# schematicEagle.net
KiCad netlist of a schematic drawn in EAGLE
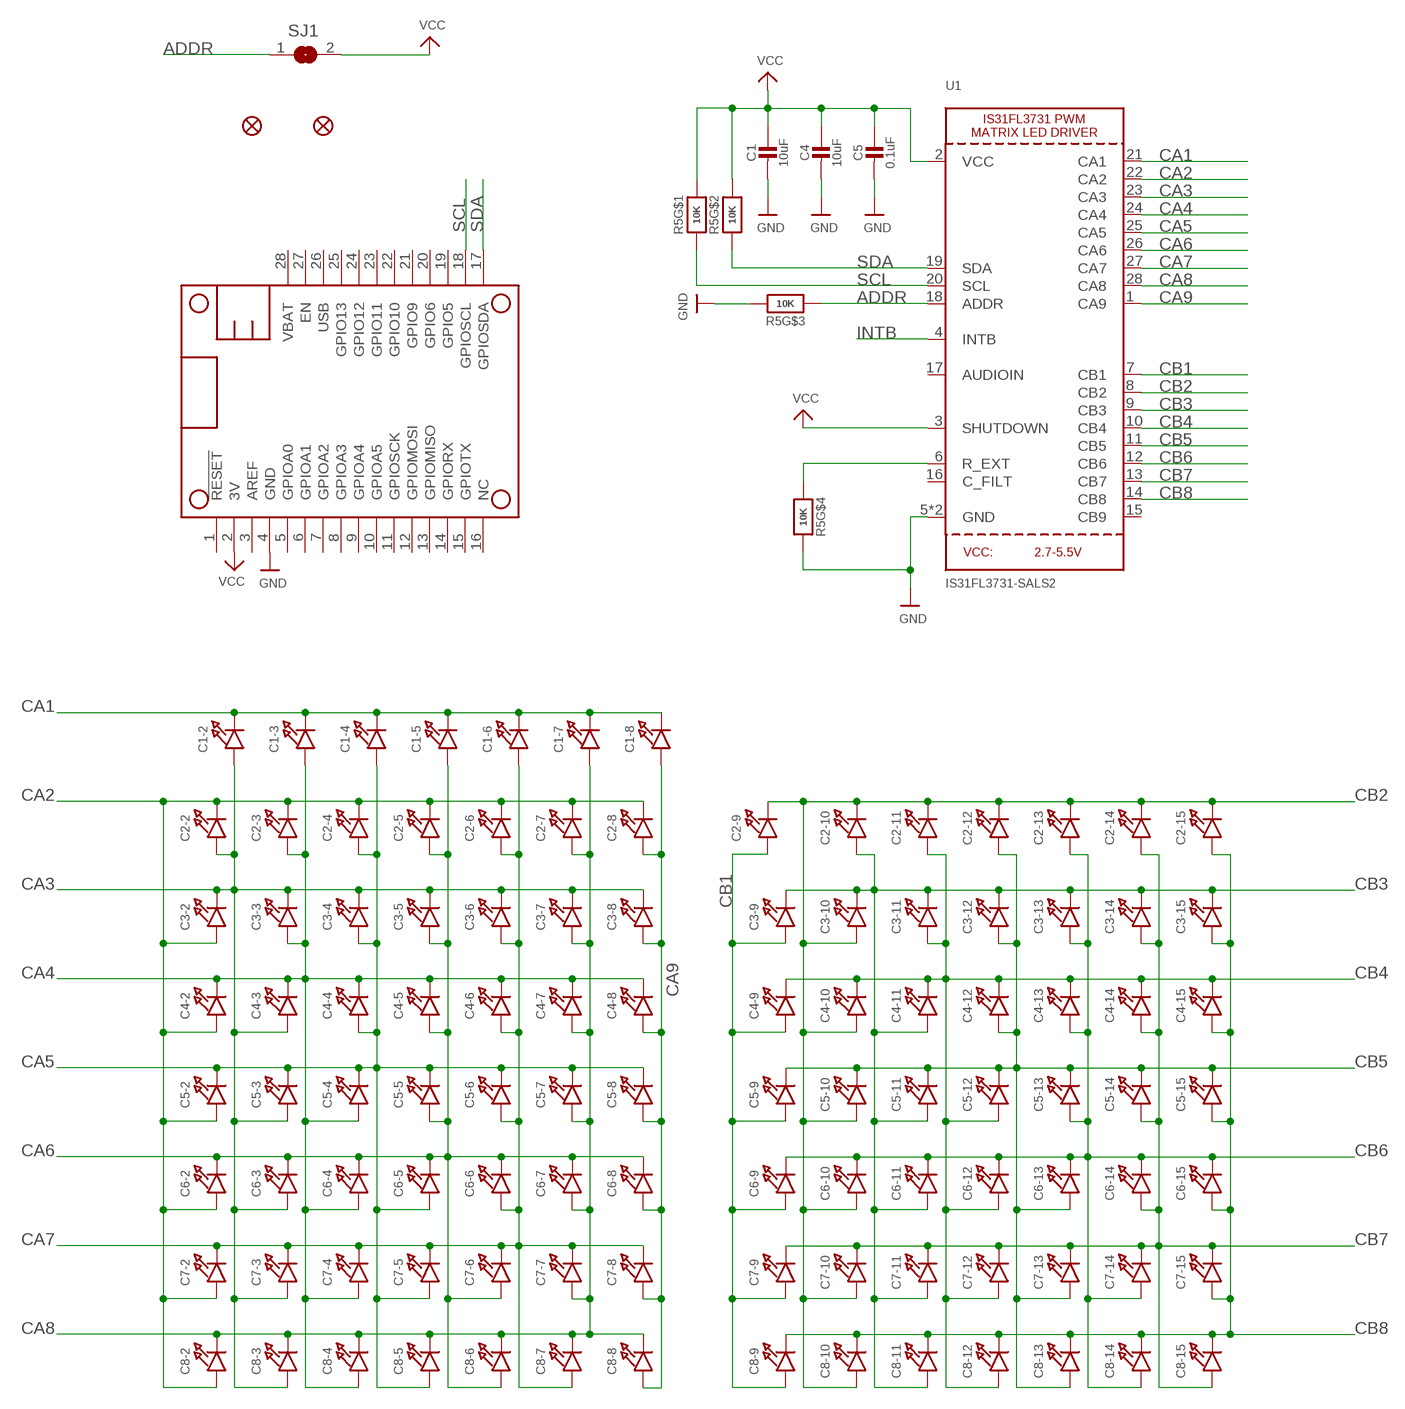
[diagram p0: schematic, sheet 1]

(export (version "E")
  (design (tool "Eeschema 10.0.6"))
  (components
    (comp (ref "C1")
      (value "10uF")
      (footprint "eagle-import:0805-NO")
      (libsource (lib "eagle-import") (part "CAP_CERAMIC0805-NOOUTLINE"))
    )
    (comp (ref "C1-2")
      (value "LED0603_NOOUTLINE")
      (footprint "eagle-import:CHIPLED_0603_NOOUTLINE")
      (libsource (lib "eagle-import") (part "LED0603_NOOUTLINE"))
    )
    (comp (ref "C1-3")
      (value "LED0603_NOOUTLINE")
      (footprint "eagle-import:CHIPLED_0603_NOOUTLINE")
      (libsource (lib "eagle-import") (part "LED0603_NOOUTLINE"))
    )
    (comp (ref "C1-4")
      (value "LED0603_NOOUTLINE")
      (footprint "eagle-import:CHIPLED_0603_NOOUTLINE")
      (libsource (lib "eagle-import") (part "LED0603_NOOUTLINE"))
    )
    (comp (ref "C1-5")
      (value "LED0603_NOOUTLINE")
      (footprint "eagle-import:CHIPLED_0603_NOOUTLINE")
      (libsource (lib "eagle-import") (part "LED0603_NOOUTLINE"))
    )
    (comp (ref "C1-6")
      (value "LED0603_NOOUTLINE")
      (footprint "eagle-import:CHIPLED_0603_NOOUTLINE")
      (libsource (lib "eagle-import") (part "LED0603_NOOUTLINE"))
    )
    (comp (ref "C1-7")
      (value "LED0603_NOOUTLINE")
      (footprint "eagle-import:CHIPLED_0603_NOOUTLINE")
      (libsource (lib "eagle-import") (part "LED0603_NOOUTLINE"))
    )
    (comp (ref "C1-8")
      (value "LED0603_NOOUTLINE")
      (footprint "eagle-import:CHIPLED_0603_NOOUTLINE")
      (libsource (lib "eagle-import") (part "LED0603_NOOUTLINE"))
    )
    (comp (ref "C2-2")
      (value "LED0603_NOOUTLINE")
      (footprint "eagle-import:CHIPLED_0603_NOOUTLINE")
      (libsource (lib "eagle-import") (part "LED0603_NOOUTLINE"))
    )
    (comp (ref "C2-3")
      (value "LED0603_NOOUTLINE")
      (footprint "eagle-import:CHIPLED_0603_NOOUTLINE")
      (libsource (lib "eagle-import") (part "LED0603_NOOUTLINE"))
    )
    (comp (ref "C2-4")
      (value "LED0603_NOOUTLINE")
      (footprint "eagle-import:CHIPLED_0603_NOOUTLINE")
      (libsource (lib "eagle-import") (part "LED0603_NOOUTLINE"))
    )
    (comp (ref "C2-5")
      (value "LED0603_NOOUTLINE")
      (footprint "eagle-import:CHIPLED_0603_NOOUTLINE")
      (libsource (lib "eagle-import") (part "LED0603_NOOUTLINE"))
    )
    (comp (ref "C2-6")
      (value "LED0603_NOOUTLINE")
      (footprint "eagle-import:CHIPLED_0603_NOOUTLINE")
      (libsource (lib "eagle-import") (part "LED0603_NOOUTLINE"))
    )
    (comp (ref "C2-7")
      (value "LED0603_NOOUTLINE")
      (footprint "eagle-import:CHIPLED_0603_NOOUTLINE")
      (libsource (lib "eagle-import") (part "LED0603_NOOUTLINE"))
    )
    (comp (ref "C2-8")
      (value "LED0603_NOOUTLINE")
      (footprint "eagle-import:CHIPLED_0603_NOOUTLINE")
      (libsource (lib "eagle-import") (part "LED0603_NOOUTLINE"))
    )
    (comp (ref "C2-9")
      (value "LED0603_NOOUTLINE")
      (footprint "eagle-import:CHIPLED_0603_NOOUTLINE")
      (libsource (lib "eagle-import") (part "LED0603_NOOUTLINE"))
    )
    (comp (ref "C2-10")
      (value "LED0603_NOOUTLINE")
      (footprint "eagle-import:CHIPLED_0603_NOOUTLINE")
      (libsource (lib "eagle-import") (part "LED0603_NOOUTLINE"))
    )
    (comp (ref "C2-11")
      (value "LED0603_NOOUTLINE")
      (footprint "eagle-import:CHIPLED_0603_NOOUTLINE")
      (libsource (lib "eagle-import") (part "LED0603_NOOUTLINE"))
    )
    (comp (ref "C2-12")
      (value "LED0603_NOOUTLINE")
      (footprint "eagle-import:CHIPLED_0603_NOOUTLINE")
      (libsource (lib "eagle-import") (part "LED0603_NOOUTLINE"))
    )
    (comp (ref "C2-13")
      (value "LED0603_NOOUTLINE")
      (footprint "eagle-import:CHIPLED_0603_NOOUTLINE")
      (libsource (lib "eagle-import") (part "LED0603_NOOUTLINE"))
    )
    (comp (ref "C2-14")
      (value "LED0603_NOOUTLINE")
      (footprint "eagle-import:CHIPLED_0603_NOOUTLINE")
      (libsource (lib "eagle-import") (part "LED0603_NOOUTLINE"))
    )
    (comp (ref "C2-15")
      (value "LED0603_NOOUTLINE")
      (footprint "eagle-import:CHIPLED_0603_NOOUTLINE")
      (libsource (lib "eagle-import") (part "LED0603_NOOUTLINE"))
    )
    (comp (ref "C3-2")
      (value "LED0603_NOOUTLINE")
      (footprint "eagle-import:CHIPLED_0603_NOOUTLINE")
      (libsource (lib "eagle-import") (part "LED0603_NOOUTLINE"))
    )
    (comp (ref "C3-3")
      (value "LED0603_NOOUTLINE")
      (footprint "eagle-import:CHIPLED_0603_NOOUTLINE")
      (libsource (lib "eagle-import") (part "LED0603_NOOUTLINE"))
    )
    (comp (ref "C3-4")
      (value "LED0603_NOOUTLINE")
      (footprint "eagle-import:CHIPLED_0603_NOOUTLINE")
      (libsource (lib "eagle-import") (part "LED0603_NOOUTLINE"))
    )
    (comp (ref "C3-5")
      (value "LED0603_NOOUTLINE")
      (footprint "eagle-import:CHIPLED_0603_NOOUTLINE")
      (libsource (lib "eagle-import") (part "LED0603_NOOUTLINE"))
    )
    (comp (ref "C3-6")
      (value "LED0603_NOOUTLINE")
      (footprint "eagle-import:CHIPLED_0603_NOOUTLINE")
      (libsource (lib "eagle-import") (part "LED0603_NOOUTLINE"))
    )
    (comp (ref "C3-7")
      (value "LED0603_NOOUTLINE")
      (footprint "eagle-import:CHIPLED_0603_NOOUTLINE")
      (libsource (lib "eagle-import") (part "LED0603_NOOUTLINE"))
    )
    (comp (ref "C3-8")
      (value "LED0603_NOOUTLINE")
      (footprint "eagle-import:CHIPLED_0603_NOOUTLINE")
      (libsource (lib "eagle-import") (part "LED0603_NOOUTLINE"))
    )
    (comp (ref "C3-9")
      (value "LED0603_NOOUTLINE")
      (footprint "eagle-import:CHIPLED_0603_NOOUTLINE")
      (libsource (lib "eagle-import") (part "LED0603_NOOUTLINE"))
    )
    (comp (ref "C3-10")
      (value "LED0603_NOOUTLINE")
      (footprint "eagle-import:CHIPLED_0603_NOOUTLINE")
      (libsource (lib "eagle-import") (part "LED0603_NOOUTLINE"))
    )
    (comp (ref "C3-11")
      (value "LED0603_NOOUTLINE")
      (footprint "eagle-import:CHIPLED_0603_NOOUTLINE")
      (libsource (lib "eagle-import") (part "LED0603_NOOUTLINE"))
    )
    (comp (ref "C3-12")
      (value "LED0603_NOOUTLINE")
      (footprint "eagle-import:CHIPLED_0603_NOOUTLINE")
      (libsource (lib "eagle-import") (part "LED0603_NOOUTLINE"))
    )
    (comp (ref "C3-13")
      (value "LED0603_NOOUTLINE")
      (footprint "eagle-import:CHIPLED_0603_NOOUTLINE")
      (libsource (lib "eagle-import") (part "LED0603_NOOUTLINE"))
    )
    (comp (ref "C3-14")
      (value "LED0603_NOOUTLINE")
      (footprint "eagle-import:CHIPLED_0603_NOOUTLINE")
      (libsource (lib "eagle-import") (part "LED0603_NOOUTLINE"))
    )
    (comp (ref "C3-15")
      (value "LED0603_NOOUTLINE")
      (footprint "eagle-import:CHIPLED_0603_NOOUTLINE")
      (libsource (lib "eagle-import") (part "LED0603_NOOUTLINE"))
    )
    (comp (ref "C4")
      (value "10uF")
      (footprint "eagle-import:0805-NO")
      (libsource (lib "eagle-import") (part "CAP_CERAMIC0805-NOOUTLINE"))
    )
    (comp (ref "C4-2")
      (value "LED0603_NOOUTLINE")
      (footprint "eagle-import:CHIPLED_0603_NOOUTLINE")
      (libsource (lib "eagle-import") (part "LED0603_NOOUTLINE"))
    )
    (comp (ref "C4-3")
      (value "LED0603_NOOUTLINE")
      (footprint "eagle-import:CHIPLED_0603_NOOUTLINE")
      (libsource (lib "eagle-import") (part "LED0603_NOOUTLINE"))
    )
    (comp (ref "C4-4")
      (value "LED0603_NOOUTLINE")
      (footprint "eagle-import:CHIPLED_0603_NOOUTLINE")
      (libsource (lib "eagle-import") (part "LED0603_NOOUTLINE"))
    )
    (comp (ref "C4-5")
      (value "LED0603_NOOUTLINE")
      (footprint "eagle-import:CHIPLED_0603_NOOUTLINE")
      (libsource (lib "eagle-import") (part "LED0603_NOOUTLINE"))
    )
    (comp (ref "C4-6")
      (value "LED0603_NOOUTLINE")
      (footprint "eagle-import:CHIPLED_0603_NOOUTLINE")
      (libsource (lib "eagle-import") (part "LED0603_NOOUTLINE"))
    )
    (comp (ref "C4-7")
      (value "LED0603_NOOUTLINE")
      (footprint "eagle-import:CHIPLED_0603_NOOUTLINE")
      (libsource (lib "eagle-import") (part "LED0603_NOOUTLINE"))
    )
    (comp (ref "C4-8")
      (value "LED0603_NOOUTLINE")
      (footprint "eagle-import:CHIPLED_0603_NOOUTLINE")
      (libsource (lib "eagle-import") (part "LED0603_NOOUTLINE"))
    )
    (comp (ref "C4-9")
      (value "LED0603_NOOUTLINE")
      (footprint "eagle-import:CHIPLED_0603_NOOUTLINE")
      (libsource (lib "eagle-import") (part "LED0603_NOOUTLINE"))
    )
    (comp (ref "C4-10")
      (value "LED0603_NOOUTLINE")
      (footprint "eagle-import:CHIPLED_0603_NOOUTLINE")
      (libsource (lib "eagle-import") (part "LED0603_NOOUTLINE"))
    )
    (comp (ref "C4-11")
      (value "LED0603_NOOUTLINE")
      (footprint "eagle-import:CHIPLED_0603_NOOUTLINE")
      (libsource (lib "eagle-import") (part "LED0603_NOOUTLINE"))
    )
    (comp (ref "C4-12")
      (value "LED0603_NOOUTLINE")
      (footprint "eagle-import:CHIPLED_0603_NOOUTLINE")
      (libsource (lib "eagle-import") (part "LED0603_NOOUTLINE"))
    )
    (comp (ref "C4-13")
      (value "LED0603_NOOUTLINE")
      (footprint "eagle-import:CHIPLED_0603_NOOUTLINE")
      (libsource (lib "eagle-import") (part "LED0603_NOOUTLINE"))
    )
    (comp (ref "C4-14")
      (value "LED0603_NOOUTLINE")
      (footprint "eagle-import:CHIPLED_0603_NOOUTLINE")
      (libsource (lib "eagle-import") (part "LED0603_NOOUTLINE"))
    )
    (comp (ref "C4-15")
      (value "LED0603_NOOUTLINE")
      (footprint "eagle-import:CHIPLED_0603_NOOUTLINE")
      (libsource (lib "eagle-import") (part "LED0603_NOOUTLINE"))
    )
    (comp (ref "C5")
      (value "0.1uF")
      (footprint "eagle-import:0805-NO")
      (libsource (lib "eagle-import") (part "CAP_CERAMIC0805-NOOUTLINE"))
    )
    (comp (ref "C5-2")
      (value "LED0603_NOOUTLINE")
      (footprint "eagle-import:CHIPLED_0603_NOOUTLINE")
      (libsource (lib "eagle-import") (part "LED0603_NOOUTLINE"))
    )
    (comp (ref "C5-3")
      (value "LED0603_NOOUTLINE")
      (footprint "eagle-import:CHIPLED_0603_NOOUTLINE")
      (libsource (lib "eagle-import") (part "LED0603_NOOUTLINE"))
    )
    (comp (ref "C5-4")
      (value "LED0603_NOOUTLINE")
      (footprint "eagle-import:CHIPLED_0603_NOOUTLINE")
      (libsource (lib "eagle-import") (part "LED0603_NOOUTLINE"))
    )
    (comp (ref "C5-5")
      (value "LED0603_NOOUTLINE")
      (footprint "eagle-import:CHIPLED_0603_NOOUTLINE")
      (libsource (lib "eagle-import") (part "LED0603_NOOUTLINE"))
    )
    (comp (ref "C5-6")
      (value "LED0603_NOOUTLINE")
      (footprint "eagle-import:CHIPLED_0603_NOOUTLINE")
      (libsource (lib "eagle-import") (part "LED0603_NOOUTLINE"))
    )
    (comp (ref "C5-7")
      (value "LED0603_NOOUTLINE")
      (footprint "eagle-import:CHIPLED_0603_NOOUTLINE")
      (libsource (lib "eagle-import") (part "LED0603_NOOUTLINE"))
    )
    (comp (ref "C5-8")
      (value "LED0603_NOOUTLINE")
      (footprint "eagle-import:CHIPLED_0603_NOOUTLINE")
      (libsource (lib "eagle-import") (part "LED0603_NOOUTLINE"))
    )
    (comp (ref "C5-9")
      (value "LED0603_NOOUTLINE")
      (footprint "eagle-import:CHIPLED_0603_NOOUTLINE")
      (libsource (lib "eagle-import") (part "LED0603_NOOUTLINE"))
    )
    (comp (ref "C5-10")
      (value "LED0603_NOOUTLINE")
      (footprint "eagle-import:CHIPLED_0603_NOOUTLINE")
      (libsource (lib "eagle-import") (part "LED0603_NOOUTLINE"))
    )
    (comp (ref "C5-11")
      (value "LED0603_NOOUTLINE")
      (footprint "eagle-import:CHIPLED_0603_NOOUTLINE")
      (libsource (lib "eagle-import") (part "LED0603_NOOUTLINE"))
    )
    (comp (ref "C5-12")
      (value "LED0603_NOOUTLINE")
      (footprint "eagle-import:CHIPLED_0603_NOOUTLINE")
      (libsource (lib "eagle-import") (part "LED0603_NOOUTLINE"))
    )
    (comp (ref "C5-13")
      (value "LED0603_NOOUTLINE")
      (footprint "eagle-import:CHIPLED_0603_NOOUTLINE")
      (libsource (lib "eagle-import") (part "LED0603_NOOUTLINE"))
    )
    (comp (ref "C5-14")
      (value "LED0603_NOOUTLINE")
      (footprint "eagle-import:CHIPLED_0603_NOOUTLINE")
      (libsource (lib "eagle-import") (part "LED0603_NOOUTLINE"))
    )
    (comp (ref "C5-15")
      (value "LED0603_NOOUTLINE")
      (footprint "eagle-import:CHIPLED_0603_NOOUTLINE")
      (libsource (lib "eagle-import") (part "LED0603_NOOUTLINE"))
    )
    (comp (ref "C6-2")
      (value "LED0603_NOOUTLINE")
      (footprint "eagle-import:CHIPLED_0603_NOOUTLINE")
      (libsource (lib "eagle-import") (part "LED0603_NOOUTLINE"))
    )
    (comp (ref "C6-3")
      (value "LED0603_NOOUTLINE")
      (footprint "eagle-import:CHIPLED_0603_NOOUTLINE")
      (libsource (lib "eagle-import") (part "LED0603_NOOUTLINE"))
    )
    (comp (ref "C6-4")
      (value "LED0603_NOOUTLINE")
      (footprint "eagle-import:CHIPLED_0603_NOOUTLINE")
      (libsource (lib "eagle-import") (part "LED0603_NOOUTLINE"))
    )
    (comp (ref "C6-5")
      (value "LED0603_NOOUTLINE")
      (footprint "eagle-import:CHIPLED_0603_NOOUTLINE")
      (libsource (lib "eagle-import") (part "LED0603_NOOUTLINE"))
    )
    (comp (ref "C6-6")
      (value "LED0603_NOOUTLINE")
      (footprint "eagle-import:CHIPLED_0603_NOOUTLINE")
      (libsource (lib "eagle-import") (part "LED0603_NOOUTLINE"))
    )
    (comp (ref "C6-7")
      (value "LED0603_NOOUTLINE")
      (footprint "eagle-import:CHIPLED_0603_NOOUTLINE")
      (libsource (lib "eagle-import") (part "LED0603_NOOUTLINE"))
    )
    (comp (ref "C6-8")
      (value "LED0603_NOOUTLINE")
      (footprint "eagle-import:CHIPLED_0603_NOOUTLINE")
      (libsource (lib "eagle-import") (part "LED0603_NOOUTLINE"))
    )
    (comp (ref "C6-9")
      (value "LED0603_NOOUTLINE")
      (footprint "eagle-import:CHIPLED_0603_NOOUTLINE")
      (libsource (lib "eagle-import") (part "LED0603_NOOUTLINE"))
    )
    (comp (ref "C6-10")
      (value "LED0603_NOOUTLINE")
      (footprint "eagle-import:CHIPLED_0603_NOOUTLINE")
      (libsource (lib "eagle-import") (part "LED0603_NOOUTLINE"))
    )
    (comp (ref "C6-11")
      (value "LED0603_NOOUTLINE")
      (footprint "eagle-import:CHIPLED_0603_NOOUTLINE")
      (libsource (lib "eagle-import") (part "LED0603_NOOUTLINE"))
    )
    (comp (ref "C6-12")
      (value "LED0603_NOOUTLINE")
      (footprint "eagle-import:CHIPLED_0603_NOOUTLINE")
      (libsource (lib "eagle-import") (part "LED0603_NOOUTLINE"))
    )
    (comp (ref "C6-13")
      (value "LED0603_NOOUTLINE")
      (footprint "eagle-import:CHIPLED_0603_NOOUTLINE")
      (libsource (lib "eagle-import") (part "LED0603_NOOUTLINE"))
    )
    (comp (ref "C6-14")
      (value "LED0603_NOOUTLINE")
      (footprint "eagle-import:CHIPLED_0603_NOOUTLINE")
      (libsource (lib "eagle-import") (part "LED0603_NOOUTLINE"))
    )
    (comp (ref "C6-15")
      (value "LED0603_NOOUTLINE")
      (footprint "eagle-import:CHIPLED_0603_NOOUTLINE")
      (libsource (lib "eagle-import") (part "LED0603_NOOUTLINE"))
    )
    (comp (ref "C7-2")
      (value "LED0603_NOOUTLINE")
      (footprint "eagle-import:CHIPLED_0603_NOOUTLINE")
      (libsource (lib "eagle-import") (part "LED0603_NOOUTLINE"))
    )
    (comp (ref "C7-3")
      (value "LED0603_NOOUTLINE")
      (footprint "eagle-import:CHIPLED_0603_NOOUTLINE")
      (libsource (lib "eagle-import") (part "LED0603_NOOUTLINE"))
    )
    (comp (ref "C7-4")
      (value "LED0603_NOOUTLINE")
      (footprint "eagle-import:CHIPLED_0603_NOOUTLINE")
      (libsource (lib "eagle-import") (part "LED0603_NOOUTLINE"))
    )
    (comp (ref "C7-5")
      (value "LED0603_NOOUTLINE")
      (footprint "eagle-import:CHIPLED_0603_NOOUTLINE")
      (libsource (lib "eagle-import") (part "LED0603_NOOUTLINE"))
    )
    (comp (ref "C7-6")
      (value "LED0603_NOOUTLINE")
      (footprint "eagle-import:CHIPLED_0603_NOOUTLINE")
      (libsource (lib "eagle-import") (part "LED0603_NOOUTLINE"))
    )
    (comp (ref "C7-7")
      (value "LED0603_NOOUTLINE")
      (footprint "eagle-import:CHIPLED_0603_NOOUTLINE")
      (libsource (lib "eagle-import") (part "LED0603_NOOUTLINE"))
    )
    (comp (ref "C7-8")
      (value "LED0603_NOOUTLINE")
      (footprint "eagle-import:CHIPLED_0603_NOOUTLINE")
      (libsource (lib "eagle-import") (part "LED0603_NOOUTLINE"))
    )
    (comp (ref "C7-9")
      (value "LED0603_NOOUTLINE")
      (footprint "eagle-import:CHIPLED_0603_NOOUTLINE")
      (libsource (lib "eagle-import") (part "LED0603_NOOUTLINE"))
    )
    (comp (ref "C7-10")
      (value "LED0603_NOOUTLINE")
      (footprint "eagle-import:CHIPLED_0603_NOOUTLINE")
      (libsource (lib "eagle-import") (part "LED0603_NOOUTLINE"))
    )
    (comp (ref "C7-11")
      (value "LED0603_NOOUTLINE")
      (footprint "eagle-import:CHIPLED_0603_NOOUTLINE")
      (libsource (lib "eagle-import") (part "LED0603_NOOUTLINE"))
    )
    (comp (ref "C7-12")
      (value "LED0603_NOOUTLINE")
      (footprint "eagle-import:CHIPLED_0603_NOOUTLINE")
      (libsource (lib "eagle-import") (part "LED0603_NOOUTLINE"))
    )
    (comp (ref "C7-13")
      (value "LED0603_NOOUTLINE")
      (footprint "eagle-import:CHIPLED_0603_NOOUTLINE")
      (libsource (lib "eagle-import") (part "LED0603_NOOUTLINE"))
    )
    (comp (ref "C7-14")
      (value "LED0603_NOOUTLINE")
      (footprint "eagle-import:CHIPLED_0603_NOOUTLINE")
      (libsource (lib "eagle-import") (part "LED0603_NOOUTLINE"))
    )
    (comp (ref "C7-15")
      (value "LED0603_NOOUTLINE")
      (footprint "eagle-import:CHIPLED_0603_NOOUTLINE")
      (libsource (lib "eagle-import") (part "LED0603_NOOUTLINE"))
    )
    (comp (ref "C8-2")
      (value "LED0603_NOOUTLINE")
      (footprint "eagle-import:CHIPLED_0603_NOOUTLINE")
      (libsource (lib "eagle-import") (part "LED0603_NOOUTLINE"))
    )
    (comp (ref "C8-3")
      (value "LED0603_NOOUTLINE")
      (footprint "eagle-import:CHIPLED_0603_NOOUTLINE")
      (libsource (lib "eagle-import") (part "LED0603_NOOUTLINE"))
    )
    (comp (ref "C8-4")
      (value "LED0603_NOOUTLINE")
      (footprint "eagle-import:CHIPLED_0603_NOOUTLINE")
      (libsource (lib "eagle-import") (part "LED0603_NOOUTLINE"))
    )
    (comp (ref "C8-5")
      (value "LED0603_NOOUTLINE")
      (footprint "eagle-import:CHIPLED_0603_NOOUTLINE")
      (libsource (lib "eagle-import") (part "LED0603_NOOUTLINE"))
    )
    (comp (ref "C8-6")
      (value "LED0603_NOOUTLINE")
      (footprint "eagle-import:CHIPLED_0603_NOOUTLINE")
      (libsource (lib "eagle-import") (part "LED0603_NOOUTLINE"))
    )
    (comp (ref "C8-7")
      (value "LED0603_NOOUTLINE")
      (footprint "eagle-import:CHIPLED_0603_NOOUTLINE")
      (libsource (lib "eagle-import") (part "LED0603_NOOUTLINE"))
    )
    (comp (ref "C8-8")
      (value "LED0603_NOOUTLINE")
      (footprint "eagle-import:CHIPLED_0603_NOOUTLINE")
      (libsource (lib "eagle-import") (part "LED0603_NOOUTLINE"))
    )
    (comp (ref "C8-9")
      (value "LED0603_NOOUTLINE")
      (footprint "eagle-import:CHIPLED_0603_NOOUTLINE")
      (libsource (lib "eagle-import") (part "LED0603_NOOUTLINE"))
    )
    (comp (ref "C8-10")
      (value "LED0603_NOOUTLINE")
      (footprint "eagle-import:CHIPLED_0603_NOOUTLINE")
      (libsource (lib "eagle-import") (part "LED0603_NOOUTLINE"))
    )
    (comp (ref "C8-11")
      (value "LED0603_NOOUTLINE")
      (footprint "eagle-import:CHIPLED_0603_NOOUTLINE")
      (libsource (lib "eagle-import") (part "LED0603_NOOUTLINE"))
    )
    (comp (ref "C8-12")
      (value "LED0603_NOOUTLINE")
      (footprint "eagle-import:CHIPLED_0603_NOOUTLINE")
      (libsource (lib "eagle-import") (part "LED0603_NOOUTLINE"))
    )
    (comp (ref "C8-13")
      (value "LED0603_NOOUTLINE")
      (footprint "eagle-import:CHIPLED_0603_NOOUTLINE")
      (libsource (lib "eagle-import") (part "LED0603_NOOUTLINE"))
    )
    (comp (ref "C8-14")
      (value "LED0603_NOOUTLINE")
      (footprint "eagle-import:CHIPLED_0603_NOOUTLINE")
      (libsource (lib "eagle-import") (part "LED0603_NOOUTLINE"))
    )
    (comp (ref "C8-15")
      (value "LED0603_NOOUTLINE")
      (footprint "eagle-import:CHIPLED_0603_NOOUTLINE")
      (libsource (lib "eagle-import") (part "LED0603_NOOUTLINE"))
    )
    (comp (ref "FID1")
      (value "FIDUCIAL\"\"")
      (footprint "eagle-import:FIDUCIAL_1MM")
      (libsource (lib "eagle-import") (part "FIDUCIAL{dblquote}{dblquote}"))
    )
    (comp (ref "FID2")
      (value "FIDUCIAL\"\"")
      (footprint "eagle-import:FIDUCIAL_1MM")
      (libsource (lib "eagle-import") (part "FIDUCIAL{dblquote}{dblquote}"))
    )
    (comp (ref "MS1")
      (value "FEATHERWING")
      (footprint "eagle-import:FEATHERWING")
      (libsource (lib "eagle-import") (part "FEATHERWING"))
    )
    (comp (ref "R5")
      (value "10K")
      (footprint "eagle-import:RESPACK_4X0603")
      (libsource (lib "eagle-import") (part "RESISTOR_4PACK"))
    )
    (comp (ref "SJ1")
      (value "SOLDERJUMPER")
      (footprint "eagle-import:SOLDERJUMPER_ARROW_NOPASTE")
      (libsource (lib "eagle-import") (part "SOLDERJUMPER"))
    )
    (comp (ref "U1")
      (value "IS31FL3731-SALS2")
      (footprint "eagle-import:QFN28_4MM_0.4MM")
      (libsource (lib "eagle-import") (part "IS31FL3731QFN"))
    )
  )
  (nets
    (net (code "1") (name "/ADDR") (class "Default")
      (node (ref "R5") (pin "3") (pinfunction "1_3") (pintype "passive"))
      (node (ref "SJ1") (pin "1") (pinfunction "1_1") (pintype "passive"))
      (node (ref "U1") (pin "18") (pinfunction "ADDR_18") (pintype "bidirectional"))
    )
    (net (code "2") (name "/CA1") (class "Default")
      (node (ref "C1-2") (pin "C") (pinfunction "C_C") (pintype "passive"))
      (node (ref "C1-3") (pin "C") (pinfunction "C_C") (pintype "passive"))
      (node (ref "C1-4") (pin "C") (pinfunction "C_C") (pintype "passive"))
      (node (ref "C1-5") (pin "C") (pinfunction "C_C") (pintype "passive"))
      (node (ref "C1-6") (pin "C") (pinfunction "C_C") (pintype "passive"))
      (node (ref "C1-7") (pin "C") (pinfunction "C_C") (pintype "passive"))
      (node (ref "C1-8") (pin "C") (pinfunction "C_C") (pintype "passive"))
      (node (ref "U1") (pin "21") (pinfunction "CA1_21") (pintype "bidirectional"))
    )
    (net (code "3") (name "/CA2") (class "Default")
      (node (ref "C2-2") (pin "C") (pinfunction "C_C") (pintype "passive"))
      (node (ref "C2-3") (pin "C") (pinfunction "C_C") (pintype "passive"))
      (node (ref "C2-4") (pin "C") (pinfunction "C_C") (pintype "passive"))
      (node (ref "C2-5") (pin "C") (pinfunction "C_C") (pintype "passive"))
      (node (ref "C2-6") (pin "C") (pinfunction "C_C") (pintype "passive"))
      (node (ref "C2-7") (pin "C") (pinfunction "C_C") (pintype "passive"))
      (node (ref "C2-8") (pin "C") (pinfunction "C_C") (pintype "passive"))
      (node (ref "C3-2") (pin "A") (pinfunction "A_A") (pintype "passive"))
      (node (ref "C4-2") (pin "A") (pinfunction "A_A") (pintype "passive"))
      (node (ref "C5-2") (pin "A") (pinfunction "A_A") (pintype "passive"))
      (node (ref "C6-2") (pin "A") (pinfunction "A_A") (pintype "passive"))
      (node (ref "C7-2") (pin "A") (pinfunction "A_A") (pintype "passive"))
      (node (ref "C8-2") (pin "A") (pinfunction "A_A") (pintype "passive"))
      (node (ref "U1") (pin "22") (pinfunction "CA2_22") (pintype "bidirectional"))
    )
    (net (code "4") (name "/CA3") (class "Default")
      (node (ref "C1-2") (pin "A") (pinfunction "A_A") (pintype "passive"))
      (node (ref "C2-2") (pin "A") (pinfunction "A_A") (pintype "passive"))
      (node (ref "C3-2") (pin "C") (pinfunction "C_C") (pintype "passive"))
      (node (ref "C3-3") (pin "C") (pinfunction "C_C") (pintype "passive"))
      (node (ref "C3-4") (pin "C") (pinfunction "C_C") (pintype "passive"))
      (node (ref "C3-5") (pin "C") (pinfunction "C_C") (pintype "passive"))
      (node (ref "C3-6") (pin "C") (pinfunction "C_C") (pintype "passive"))
      (node (ref "C3-7") (pin "C") (pinfunction "C_C") (pintype "passive"))
      (node (ref "C3-8") (pin "C") (pinfunction "C_C") (pintype "passive"))
      (node (ref "C4-3") (pin "A") (pinfunction "A_A") (pintype "passive"))
      (node (ref "C5-3") (pin "A") (pinfunction "A_A") (pintype "passive"))
      (node (ref "C6-3") (pin "A") (pinfunction "A_A") (pintype "passive"))
      (node (ref "C7-3") (pin "A") (pinfunction "A_A") (pintype "passive"))
      (node (ref "C8-3") (pin "A") (pinfunction "A_A") (pintype "passive"))
      (node (ref "U1") (pin "23") (pinfunction "CA3_23") (pintype "bidirectional"))
    )
    (net (code "5") (name "/CA4") (class "Default")
      (node (ref "C1-3") (pin "A") (pinfunction "A_A") (pintype "passive"))
      (node (ref "C2-3") (pin "A") (pinfunction "A_A") (pintype "passive"))
      (node (ref "C3-3") (pin "A") (pinfunction "A_A") (pintype "passive"))
      (node (ref "C4-2") (pin "C") (pinfunction "C_C") (pintype "passive"))
      (node (ref "C4-3") (pin "C") (pinfunction "C_C") (pintype "passive"))
      (node (ref "C4-4") (pin "C") (pinfunction "C_C") (pintype "passive"))
      (node (ref "C4-5") (pin "C") (pinfunction "C_C") (pintype "passive"))
      (node (ref "C4-6") (pin "C") (pinfunction "C_C") (pintype "passive"))
      (node (ref "C4-7") (pin "C") (pinfunction "C_C") (pintype "passive"))
      (node (ref "C4-8") (pin "C") (pinfunction "C_C") (pintype "passive"))
      (node (ref "C5-4") (pin "A") (pinfunction "A_A") (pintype "passive"))
      (node (ref "C6-4") (pin "A") (pinfunction "A_A") (pintype "passive"))
      (node (ref "C7-4") (pin "A") (pinfunction "A_A") (pintype "passive"))
      (node (ref "C8-4") (pin "A") (pinfunction "A_A") (pintype "passive"))
      (node (ref "U1") (pin "24") (pinfunction "CA4_24") (pintype "bidirectional"))
    )
    (net (code "6") (name "/CA5") (class "Default")
      (node (ref "C1-4") (pin "A") (pinfunction "A_A") (pintype "passive"))
      (node (ref "C2-4") (pin "A") (pinfunction "A_A") (pintype "passive"))
      (node (ref "C3-4") (pin "A") (pinfunction "A_A") (pintype "passive"))
      (node (ref "C4-4") (pin "A") (pinfunction "A_A") (pintype "passive"))
      (node (ref "C5-2") (pin "C") (pinfunction "C_C") (pintype "passive"))
      (node (ref "C5-3") (pin "C") (pinfunction "C_C") (pintype "passive"))
      (node (ref "C5-4") (pin "C") (pinfunction "C_C") (pintype "passive"))
      (node (ref "C5-5") (pin "C") (pinfunction "C_C") (pintype "passive"))
      (node (ref "C5-6") (pin "C") (pinfunction "C_C") (pintype "passive"))
      (node (ref "C5-7") (pin "C") (pinfunction "C_C") (pintype "passive"))
      (node (ref "C5-8") (pin "C") (pinfunction "C_C") (pintype "passive"))
      (node (ref "C6-5") (pin "A") (pinfunction "A_A") (pintype "passive"))
      (node (ref "C7-5") (pin "A") (pinfunction "A_A") (pintype "passive"))
      (node (ref "C8-5") (pin "A") (pinfunction "A_A") (pintype "passive"))
      (node (ref "U1") (pin "25") (pinfunction "CA5_25") (pintype "bidirectional"))
    )
    (net (code "7") (name "/CA6") (class "Default")
      (node (ref "C1-5") (pin "A") (pinfunction "A_A") (pintype "passive"))
      (node (ref "C2-5") (pin "A") (pinfunction "A_A") (pintype "passive"))
      (node (ref "C3-5") (pin "A") (pinfunction "A_A") (pintype "passive"))
      (node (ref "C4-5") (pin "A") (pinfunction "A_A") (pintype "passive"))
      (node (ref "C5-5") (pin "A") (pinfunction "A_A") (pintype "passive"))
      (node (ref "C6-2") (pin "C") (pinfunction "C_C") (pintype "passive"))
      (node (ref "C6-3") (pin "C") (pinfunction "C_C") (pintype "passive"))
      (node (ref "C6-4") (pin "C") (pinfunction "C_C") (pintype "passive"))
      (node (ref "C6-5") (pin "C") (pinfunction "C_C") (pintype "passive"))
      (node (ref "C6-6") (pin "C") (pinfunction "C_C") (pintype "passive"))
      (node (ref "C6-7") (pin "C") (pinfunction "C_C") (pintype "passive"))
      (node (ref "C6-8") (pin "C") (pinfunction "C_C") (pintype "passive"))
      (node (ref "C7-6") (pin "A") (pinfunction "A_A") (pintype "passive"))
      (node (ref "C8-6") (pin "A") (pinfunction "A_A") (pintype "passive"))
      (node (ref "U1") (pin "26") (pinfunction "CA6_26") (pintype "bidirectional"))
    )
    (net (code "8") (name "/CA7") (class "Default")
      (node (ref "C1-6") (pin "A") (pinfunction "A_A") (pintype "passive"))
      (node (ref "C2-6") (pin "A") (pinfunction "A_A") (pintype "passive"))
      (node (ref "C3-6") (pin "A") (pinfunction "A_A") (pintype "passive"))
      (node (ref "C4-6") (pin "A") (pinfunction "A_A") (pintype "passive"))
      (node (ref "C5-6") (pin "A") (pinfunction "A_A") (pintype "passive"))
      (node (ref "C6-6") (pin "A") (pinfunction "A_A") (pintype "passive"))
      (node (ref "C7-2") (pin "C") (pinfunction "C_C") (pintype "passive"))
      (node (ref "C7-3") (pin "C") (pinfunction "C_C") (pintype "passive"))
      (node (ref "C7-4") (pin "C") (pinfunction "C_C") (pintype "passive"))
      (node (ref "C7-5") (pin "C") (pinfunction "C_C") (pintype "passive"))
      (node (ref "C7-6") (pin "C") (pinfunction "C_C") (pintype "passive"))
      (node (ref "C7-7") (pin "C") (pinfunction "C_C") (pintype "passive"))
      (node (ref "C7-8") (pin "C") (pinfunction "C_C") (pintype "passive"))
      (node (ref "C8-7") (pin "A") (pinfunction "A_A") (pintype "passive"))
      (node (ref "U1") (pin "27") (pinfunction "CA7_27") (pintype "bidirectional"))
    )
    (net (code "9") (name "/CA8") (class "Default")
      (node (ref "C1-7") (pin "A") (pinfunction "A_A") (pintype "passive"))
      (node (ref "C2-7") (pin "A") (pinfunction "A_A") (pintype "passive"))
      (node (ref "C3-7") (pin "A") (pinfunction "A_A") (pintype "passive"))
      (node (ref "C4-7") (pin "A") (pinfunction "A_A") (pintype "passive"))
      (node (ref "C5-7") (pin "A") (pinfunction "A_A") (pintype "passive"))
      (node (ref "C6-7") (pin "A") (pinfunction "A_A") (pintype "passive"))
      (node (ref "C7-7") (pin "A") (pinfunction "A_A") (pintype "passive"))
      (node (ref "C8-2") (pin "C") (pinfunction "C_C") (pintype "passive"))
      (node (ref "C8-3") (pin "C") (pinfunction "C_C") (pintype "passive"))
      (node (ref "C8-4") (pin "C") (pinfunction "C_C") (pintype "passive"))
      (node (ref "C8-5") (pin "C") (pinfunction "C_C") (pintype "passive"))
      (node (ref "C8-6") (pin "C") (pinfunction "C_C") (pintype "passive"))
      (node (ref "C8-7") (pin "C") (pinfunction "C_C") (pintype "passive"))
      (node (ref "C8-8") (pin "C") (pinfunction "C_C") (pintype "passive"))
      (node (ref "U1") (pin "28") (pinfunction "CA8_28") (pintype "bidirectional"))
    )
    (net (code "10") (name "/CA9") (class "Default")
      (node (ref "C1-8") (pin "A") (pinfunction "A_A") (pintype "passive"))
      (node (ref "C2-8") (pin "A") (pinfunction "A_A") (pintype "passive"))
      (node (ref "C3-8") (pin "A") (pinfunction "A_A") (pintype "passive"))
      (node (ref "C4-8") (pin "A") (pinfunction "A_A") (pintype "passive"))
      (node (ref "C5-8") (pin "A") (pinfunction "A_A") (pintype "passive"))
      (node (ref "C6-8") (pin "A") (pinfunction "A_A") (pintype "passive"))
      (node (ref "C7-8") (pin "A") (pinfunction "A_A") (pintype "passive"))
      (node (ref "C8-8") (pin "A") (pinfunction "A_A") (pintype "passive"))
      (node (ref "U1") (pin "1") (pinfunction "CA9_1") (pintype "bidirectional"))
    )
    (net (code "11") (name "/CB1") (class "Default")
      (node (ref "C2-9") (pin "A") (pinfunction "A_A") (pintype "passive"))
      (node (ref "C3-9") (pin "A") (pinfunction "A_A") (pintype "passive"))
      (node (ref "C4-9") (pin "A") (pinfunction "A_A") (pintype "passive"))
      (node (ref "C5-9") (pin "A") (pinfunction "A_A") (pintype "passive"))
      (node (ref "C6-9") (pin "A") (pinfunction "A_A") (pintype "passive"))
      (node (ref "C7-9") (pin "A") (pinfunction "A_A") (pintype "passive"))
      (node (ref "C8-9") (pin "A") (pinfunction "A_A") (pintype "passive"))
      (node (ref "U1") (pin "7") (pinfunction "CB1_7") (pintype "bidirectional"))
    )
    (net (code "12") (name "/CB2") (class "Default")
      (node (ref "C2-10") (pin "C") (pinfunction "C_C") (pintype "passive"))
      (node (ref "C2-11") (pin "C") (pinfunction "C_C") (pintype "passive"))
      (node (ref "C2-12") (pin "C") (pinfunction "C_C") (pintype "passive"))
      (node (ref "C2-13") (pin "C") (pinfunction "C_C") (pintype "passive"))
      (node (ref "C2-14") (pin "C") (pinfunction "C_C") (pintype "passive"))
      (node (ref "C2-15") (pin "C") (pinfunction "C_C") (pintype "passive"))
      (node (ref "C2-9") (pin "C") (pinfunction "C_C") (pintype "passive"))
      (node (ref "C3-10") (pin "A") (pinfunction "A_A") (pintype "passive"))
      (node (ref "C4-10") (pin "A") (pinfunction "A_A") (pintype "passive"))
      (node (ref "C5-10") (pin "A") (pinfunction "A_A") (pintype "passive"))
      (node (ref "C6-10") (pin "A") (pinfunction "A_A") (pintype "passive"))
      (node (ref "C7-10") (pin "A") (pinfunction "A_A") (pintype "passive"))
      (node (ref "C8-10") (pin "A") (pinfunction "A_A") (pintype "passive"))
      (node (ref "U1") (pin "8") (pinfunction "CB2_8") (pintype "bidirectional"))
    )
    (net (code "13") (name "/CB3") (class "Default")
      (node (ref "C2-10") (pin "A") (pinfunction "A_A") (pintype "passive"))
      (node (ref "C3-10") (pin "C") (pinfunction "C_C") (pintype "passive"))
      (node (ref "C3-11") (pin "C") (pinfunction "C_C") (pintype "passive"))
      (node (ref "C3-12") (pin "C") (pinfunction "C_C") (pintype "passive"))
      (node (ref "C3-13") (pin "C") (pinfunction "C_C") (pintype "passive"))
      (node (ref "C3-14") (pin "C") (pinfunction "C_C") (pintype "passive"))
      (node (ref "C3-15") (pin "C") (pinfunction "C_C") (pintype "passive"))
      (node (ref "C3-9") (pin "C") (pinfunction "C_C") (pintype "passive"))
      (node (ref "C4-11") (pin "A") (pinfunction "A_A") (pintype "passive"))
      (node (ref "C5-11") (pin "A") (pinfunction "A_A") (pintype "passive"))
      (node (ref "C6-11") (pin "A") (pinfunction "A_A") (pintype "passive"))
      (node (ref "C7-11") (pin "A") (pinfunction "A_A") (pintype "passive"))
      (node (ref "C8-11") (pin "A") (pinfunction "A_A") (pintype "passive"))
      (node (ref "U1") (pin "9") (pinfunction "CB3_9") (pintype "bidirectional"))
    )
    (net (code "14") (name "/CB4") (class "Default")
      (node (ref "C2-11") (pin "A") (pinfunction "A_A") (pintype "passive"))
      (node (ref "C3-11") (pin "A") (pinfunction "A_A") (pintype "passive"))
      (node (ref "C4-10") (pin "C") (pinfunction "C_C") (pintype "passive"))
      (node (ref "C4-11") (pin "C") (pinfunction "C_C") (pintype "passive"))
      (node (ref "C4-12") (pin "C") (pinfunction "C_C") (pintype "passive"))
      (node (ref "C4-13") (pin "C") (pinfunction "C_C") (pintype "passive"))
      (node (ref "C4-14") (pin "C") (pinfunction "C_C") (pintype "passive"))
      (node (ref "C4-15") (pin "C") (pinfunction "C_C") (pintype "passive"))
      (node (ref "C4-9") (pin "C") (pinfunction "C_C") (pintype "passive"))
      (node (ref "C5-12") (pin "A") (pinfunction "A_A") (pintype "passive"))
      (node (ref "C6-12") (pin "A") (pinfunction "A_A") (pintype "passive"))
      (node (ref "C7-12") (pin "A") (pinfunction "A_A") (pintype "passive"))
      (node (ref "C8-12") (pin "A") (pinfunction "A_A") (pintype "passive"))
      (node (ref "U1") (pin "10") (pinfunction "CB4_10") (pintype "bidirectional"))
    )
    (net (code "15") (name "/CB5") (class "Default")
      (node (ref "C2-12") (pin "A") (pinfunction "A_A") (pintype "passive"))
      (node (ref "C3-12") (pin "A") (pinfunction "A_A") (pintype "passive"))
      (node (ref "C4-12") (pin "A") (pinfunction "A_A") (pintype "passive"))
      (node (ref "C5-10") (pin "C") (pinfunction "C_C") (pintype "passive"))
      (node (ref "C5-11") (pin "C") (pinfunction "C_C") (pintype "passive"))
      (node (ref "C5-12") (pin "C") (pinfunction "C_C") (pintype "passive"))
      (node (ref "C5-13") (pin "C") (pinfunction "C_C") (pintype "passive"))
      (node (ref "C5-14") (pin "C") (pinfunction "C_C") (pintype "passive"))
      (node (ref "C5-15") (pin "C") (pinfunction "C_C") (pintype "passive"))
      (node (ref "C5-9") (pin "C") (pinfunction "C_C") (pintype "passive"))
      (node (ref "C6-13") (pin "A") (pinfunction "A_A") (pintype "passive"))
      (node (ref "C7-13") (pin "A") (pinfunction "A_A") (pintype "passive"))
      (node (ref "C8-13") (pin "A") (pinfunction "A_A") (pintype "passive"))
      (node (ref "U1") (pin "11") (pinfunction "CB5_11") (pintype "bidirectional"))
    )
    (net (code "16") (name "/CB6") (class "Default")
      (node (ref "C2-13") (pin "A") (pinfunction "A_A") (pintype "passive"))
      (node (ref "C3-13") (pin "A") (pinfunction "A_A") (pintype "passive"))
      (node (ref "C4-13") (pin "A") (pinfunction "A_A") (pintype "passive"))
      (node (ref "C5-13") (pin "A") (pinfunction "A_A") (pintype "passive"))
      (node (ref "C6-10") (pin "C") (pinfunction "C_C") (pintype "passive"))
      (node (ref "C6-11") (pin "C") (pinfunction "C_C") (pintype "passive"))
      (node (ref "C6-12") (pin "C") (pinfunction "C_C") (pintype "passive"))
      (node (ref "C6-13") (pin "C") (pinfunction "C_C") (pintype "passive"))
      (node (ref "C6-14") (pin "C") (pinfunction "C_C") (pintype "passive"))
      (node (ref "C6-15") (pin "C") (pinfunction "C_C") (pintype "passive"))
      (node (ref "C6-9") (pin "C") (pinfunction "C_C") (pintype "passive"))
      (node (ref "C7-14") (pin "A") (pinfunction "A_A") (pintype "passive"))
      (node (ref "C8-14") (pin "A") (pinfunction "A_A") (pintype "passive"))
      (node (ref "U1") (pin "12") (pinfunction "CB6_12") (pintype "bidirectional"))
    )
    (net (code "17") (name "/CB7") (class "Default")
      (node (ref "C2-14") (pin "A") (pinfunction "A_A") (pintype "passive"))
      (node (ref "C3-14") (pin "A") (pinfunction "A_A") (pintype "passive"))
      (node (ref "C4-14") (pin "A") (pinfunction "A_A") (pintype "passive"))
      (node (ref "C5-14") (pin "A") (pinfunction "A_A") (pintype "passive"))
      (node (ref "C6-14") (pin "A") (pinfunction "A_A") (pintype "passive"))
      (node (ref "C7-10") (pin "C") (pinfunction "C_C") (pintype "passive"))
      (node (ref "C7-11") (pin "C") (pinfunction "C_C") (pintype "passive"))
      (node (ref "C7-12") (pin "C") (pinfunction "C_C") (pintype "passive"))
      (node (ref "C7-13") (pin "C") (pinfunction "C_C") (pintype "passive"))
      (node (ref "C7-14") (pin "C") (pinfunction "C_C") (pintype "passive"))
      (node (ref "C7-15") (pin "C") (pinfunction "C_C") (pintype "passive"))
      (node (ref "C7-9") (pin "C") (pinfunction "C_C") (pintype "passive"))
      (node (ref "C8-15") (pin "A") (pinfunction "A_A") (pintype "passive"))
      (node (ref "U1") (pin "13") (pinfunction "CB7_13") (pintype "bidirectional"))
    )
    (net (code "18") (name "/CB8") (class "Default")
      (node (ref "C2-15") (pin "A") (pinfunction "A_A") (pintype "passive"))
      (node (ref "C3-15") (pin "A") (pinfunction "A_A") (pintype "passive"))
      (node (ref "C4-15") (pin "A") (pinfunction "A_A") (pintype "passive"))
      (node (ref "C5-15") (pin "A") (pinfunction "A_A") (pintype "passive"))
      (node (ref "C6-15") (pin "A") (pinfunction "A_A") (pintype "passive"))
      (node (ref "C7-15") (pin "A") (pinfunction "A_A") (pintype "passive"))
      (node (ref "C8-10") (pin "C") (pinfunction "C_C") (pintype "passive"))
      (node (ref "C8-11") (pin "C") (pinfunction "C_C") (pintype "passive"))
      (node (ref "C8-12") (pin "C") (pinfunction "C_C") (pintype "passive"))
      (node (ref "C8-13") (pin "C") (pinfunction "C_C") (pintype "passive"))
      (node (ref "C8-14") (pin "C") (pinfunction "C_C") (pintype "passive"))
      (node (ref "C8-15") (pin "C") (pinfunction "C_C") (pintype "passive"))
      (node (ref "C8-9") (pin "C") (pinfunction "C_C") (pintype "passive"))
      (node (ref "U1") (pin "14") (pinfunction "CB8_14") (pintype "bidirectional"))
    )
    (net (code "19") (name "/INTB") (class "Default")
      (node (ref "U1") (pin "4") (pinfunction "INTB_4") (pintype "output"))
    )
    (net (code "20") (name "/SCL") (class "Default")
      (node (ref "MS1") (pin "18") (pinfunction "GPIOSCL_18") (pintype "bidirectional"))
      (node (ref "R5") (pin "1") (pinfunction "1_1") (pintype "passive"))
      (node (ref "U1") (pin "20") (pinfunction "SCL_20") (pintype "bidirectional"))
    )
    (net (code "21") (name "/SDA") (class "Default")
      (node (ref "MS1") (pin "17") (pinfunction "GPIOSDA_17") (pintype "bidirectional"))
      (node (ref "R5") (pin "2") (pinfunction "1_2") (pintype "passive"))
      (node (ref "U1") (pin "19") (pinfunction "SDA_19") (pintype "bidirectional"))
    )
    (net (code "22") (name "/USB") (class "Default")
      (node (ref "MS1") (pin "26") (pinfunction "USB_26") (pintype "power_in"))
    )
    (net (code "23") (name "/VBAT") (class "Default")
      (node (ref "MS1") (pin "28") (pinfunction "VBAT_28") (pintype "power_in"))
    )
    (net (code "24") (name "GND") (class "Default")
      (node (ref "C1") (pin "2") (pinfunction "2_2") (pintype "passive"))
      (node (ref "C4") (pin "2") (pinfunction "2_2") (pintype "passive"))
      (node (ref "C5") (pin "2") (pinfunction "2_2") (pintype "passive"))
      (node (ref "MS1") (pin "4") (pinfunction "GND_4") (pintype "power_in"))
      (node (ref "R5") (pin "5") (pinfunction "2_5") (pintype "passive"))
      (node (ref "R5") (pin "6") (pinfunction "2_6") (pintype "passive"))
      (node (ref "U1") (pin "5") (pinfunction "GND_5") (pintype "power_in"))
      (node (ref "U1") (pin "THERMAL") (pinfunction "GND_THERMAL") (pintype "power_in"))
    )
    (net (code "25") (name "Net-(R5D-1)") (class "Default")
      (node (ref "R5") (pin "4") (pinfunction "1_4") (pintype "passive"))
      (node (ref "U1") (pin "6") (pinfunction "R_EXT_6") (pintype "bidirectional"))
    )
    (net (code "26") (name "VCC") (class "Default")
      (node (ref "C1") (pin "1") (pinfunction "1_1") (pintype "passive"))
      (node (ref "C4") (pin "1") (pinfunction "1_1") (pintype "passive"))
      (node (ref "C5") (pin "1") (pinfunction "1_1") (pintype "passive"))
      (node (ref "MS1") (pin "2") (pinfunction "3V_2") (pintype "power_in"))
      (node (ref "R5") (pin "7") (pinfunction "2_7") (pintype "passive"))
      (node (ref "R5") (pin "8") (pinfunction "2_8") (pintype "passive"))
      (node (ref "SJ1") (pin "2") (pinfunction "2_2") (pintype "passive"))
      (node (ref "U1") (pin "2") (pinfunction "VCC_2") (pintype "power_in"))
      (node (ref "U1") (pin "3") (pinfunction "SHUTDOWN_3") (pintype "input"))
    )
    (net (code "27") (name "unconnected-(MS1-AREF-Pad3)") (class "Default")
      (node (ref "MS1") (pin "3") (pinfunction "AREF_3") (pintype "passive"))
    )
    (net (code "28") (name "unconnected-(MS1-EN-Pad27)") (class "Default")
      (node (ref "MS1") (pin "27") (pinfunction "EN_27") (pintype "passive"))
    )
    (net (code "29") (name "unconnected-(MS1-GPIO5-Pad19)") (class "Default")
      (node (ref "MS1") (pin "19") (pinfunction "GPIO5_19") (pintype "bidirectional"))
    )
    (net (code "30") (name "unconnected-(MS1-GPIO6-Pad20)") (class "Default")
      (node (ref "MS1") (pin "20") (pinfunction "GPIO6_20") (pintype "bidirectional"))
    )
    (net (code "31") (name "unconnected-(MS1-GPIO9-Pad21)") (class "Default")
      (node (ref "MS1") (pin "21") (pinfunction "GPIO9_21") (pintype "bidirectional"))
    )
    (net (code "32") (name "unconnected-(MS1-GPIO10-Pad22)") (class "Default")
      (node (ref "MS1") (pin "22") (pinfunction "GPIO10_22") (pintype "bidirectional"))
    )
    (net (code "33") (name "unconnected-(MS1-GPIO11-Pad23)") (class "Default")
      (node (ref "MS1") (pin "23") (pinfunction "GPIO11_23") (pintype "bidirectional"))
    )
    (net (code "34") (name "unconnected-(MS1-GPIO12-Pad24)") (class "Default")
      (node (ref "MS1") (pin "24") (pinfunction "GPIO12_24") (pintype "bidirectional"))
    )
    (net (code "35") (name "unconnected-(MS1-GPIO13-Pad25)") (class "Default")
      (node (ref "MS1") (pin "25") (pinfunction "GPIO13_25") (pintype "bidirectional"))
    )
    (net (code "36") (name "unconnected-(MS1-GPIOA0-Pad5)") (class "Default")
      (node (ref "MS1") (pin "5") (pinfunction "GPIOA0_5") (pintype "bidirectional"))
    )
    (net (code "37") (name "unconnected-(MS1-GPIOA1-Pad6)") (class "Default")
      (node (ref "MS1") (pin "6") (pinfunction "GPIOA1_6") (pintype "bidirectional"))
    )
    (net (code "38") (name "unconnected-(MS1-GPIOA2-Pad7)") (class "Default")
      (node (ref "MS1") (pin "7") (pinfunction "GPIOA2_7") (pintype "bidirectional"))
    )
    (net (code "39") (name "unconnected-(MS1-GPIOA3-Pad8)") (class "Default")
      (node (ref "MS1") (pin "8") (pinfunction "GPIOA3_8") (pintype "bidirectional"))
    )
    (net (code "40") (name "unconnected-(MS1-GPIOA4-Pad9)") (class "Default")
      (node (ref "MS1") (pin "9") (pinfunction "GPIOA4_9") (pintype "bidirectional"))
    )
    (net (code "41") (name "unconnected-(MS1-GPIOA5-Pad10)") (class "Default")
      (node (ref "MS1") (pin "10") (pinfunction "GPIOA5_10") (pintype "bidirectional"))
    )
    (net (code "42") (name "unconnected-(MS1-GPIOMISO-Pad13)") (class "Default")
      (node (ref "MS1") (pin "13") (pinfunction "GPIOMISO_13") (pintype "bidirectional"))
    )
    (net (code "43") (name "unconnected-(MS1-GPIOMOSI-Pad12)") (class "Default")
      (node (ref "MS1") (pin "12") (pinfunction "GPIOMOSI_12") (pintype "bidirectional"))
    )
    (net (code "44") (name "unconnected-(MS1-GPIORX-Pad14)") (class "Default")
      (node (ref "MS1") (pin "14") (pinfunction "GPIORX_14") (pintype "bidirectional"))
    )
    (net (code "45") (name "unconnected-(MS1-GPIOSCK-Pad11)") (class "Default")
      (node (ref "MS1") (pin "11") (pinfunction "GPIOSCK_11") (pintype "bidirectional"))
    )
    (net (code "46") (name "unconnected-(MS1-GPIOTX-Pad15)") (class "Default")
      (node (ref "MS1") (pin "15") (pinfunction "GPIOTX_15") (pintype "bidirectional"))
    )
    (net (code "47") (name "unconnected-(MS1-NC-Pad16)") (class "Default")
      (node (ref "MS1") (pin "16") (pinfunction "NC_16") (pintype "passive"))
    )
    (net (code "48") (name "unconnected-(MS1-~{RESET}-Pad1)") (class "Default")
      (node (ref "MS1") (pin "1") (pinfunction "~{RESET}_1") (pintype "input"))
    )
    (net (code "49") (name "unconnected-(U1-AUDIOIN-Pad17)") (class "Default")
      (node (ref "U1") (pin "17") (pinfunction "AUDIOIN_17") (pintype "input"))
    )
    (net (code "50") (name "unconnected-(U1-CB9-Pad15)") (class "Default")
      (node (ref "U1") (pin "15") (pinfunction "CB9_15") (pintype "bidirectional"))
    )
    (net (code "51") (name "unconnected-(U1-C_FILT-Pad16)") (class "Default")
      (node (ref "U1") (pin "16") (pinfunction "C_FILT_16") (pintype "bidirectional"))
    )
  )
)
